# DockStation.net
KiCad netlist of a schematic drawn in Altium Designer
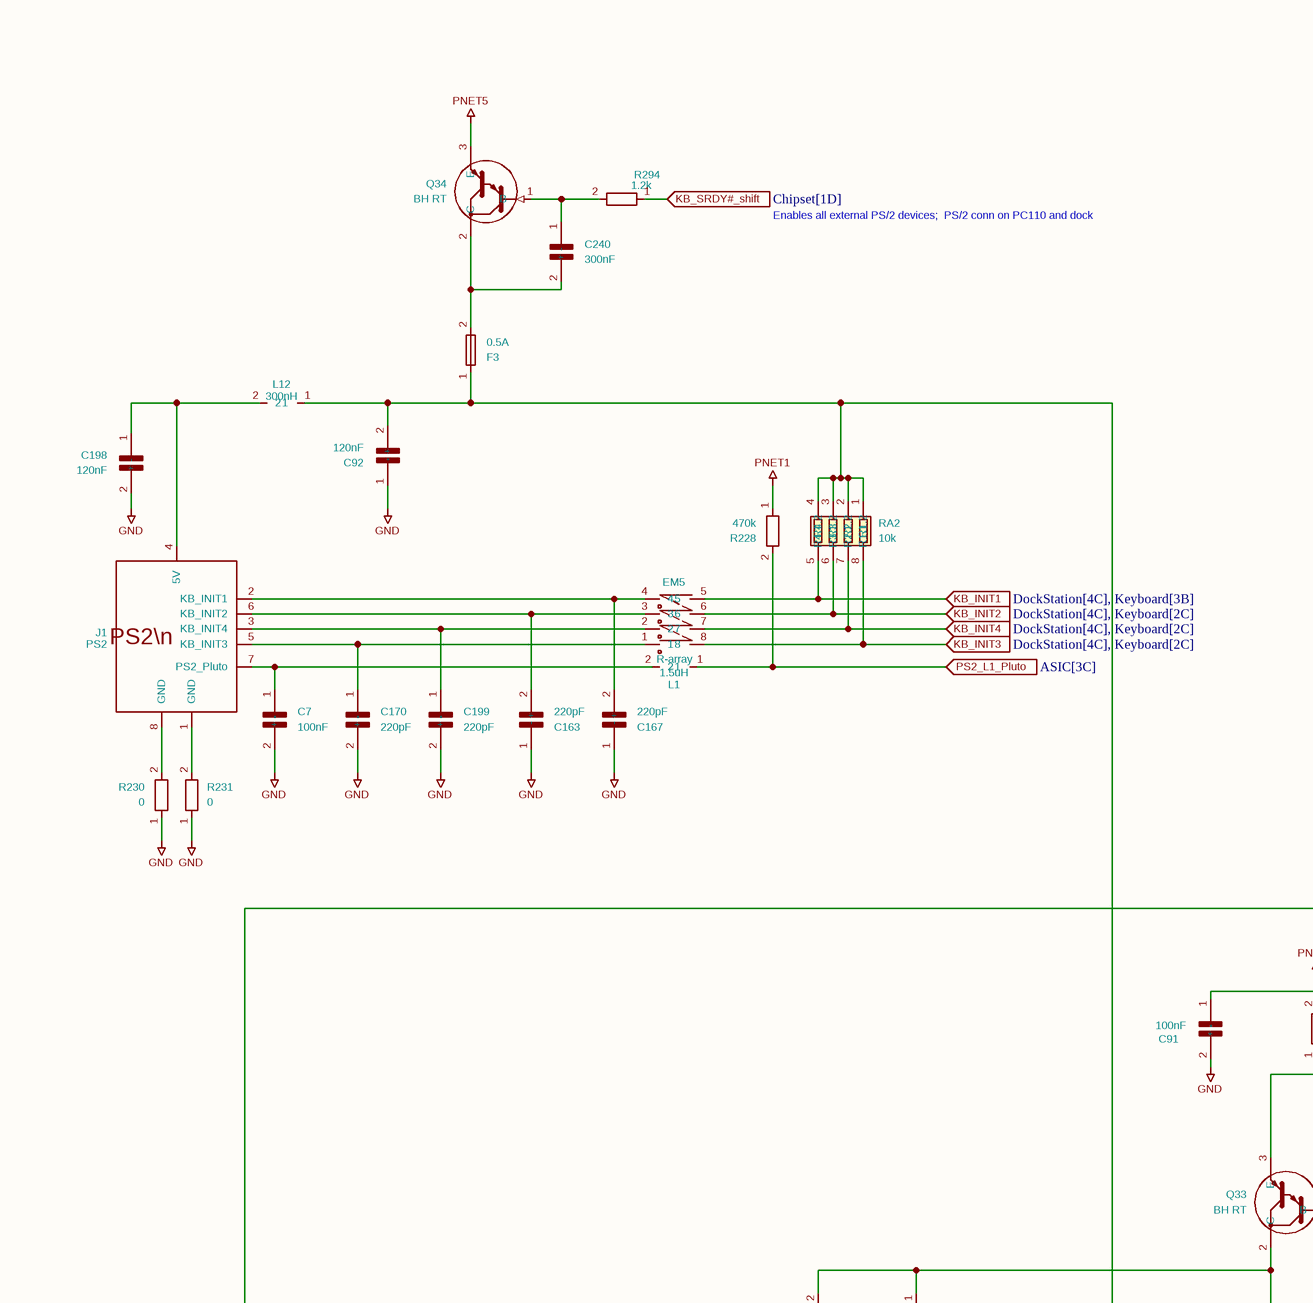
[diagram p0: DockStation.SchDoc, top left]
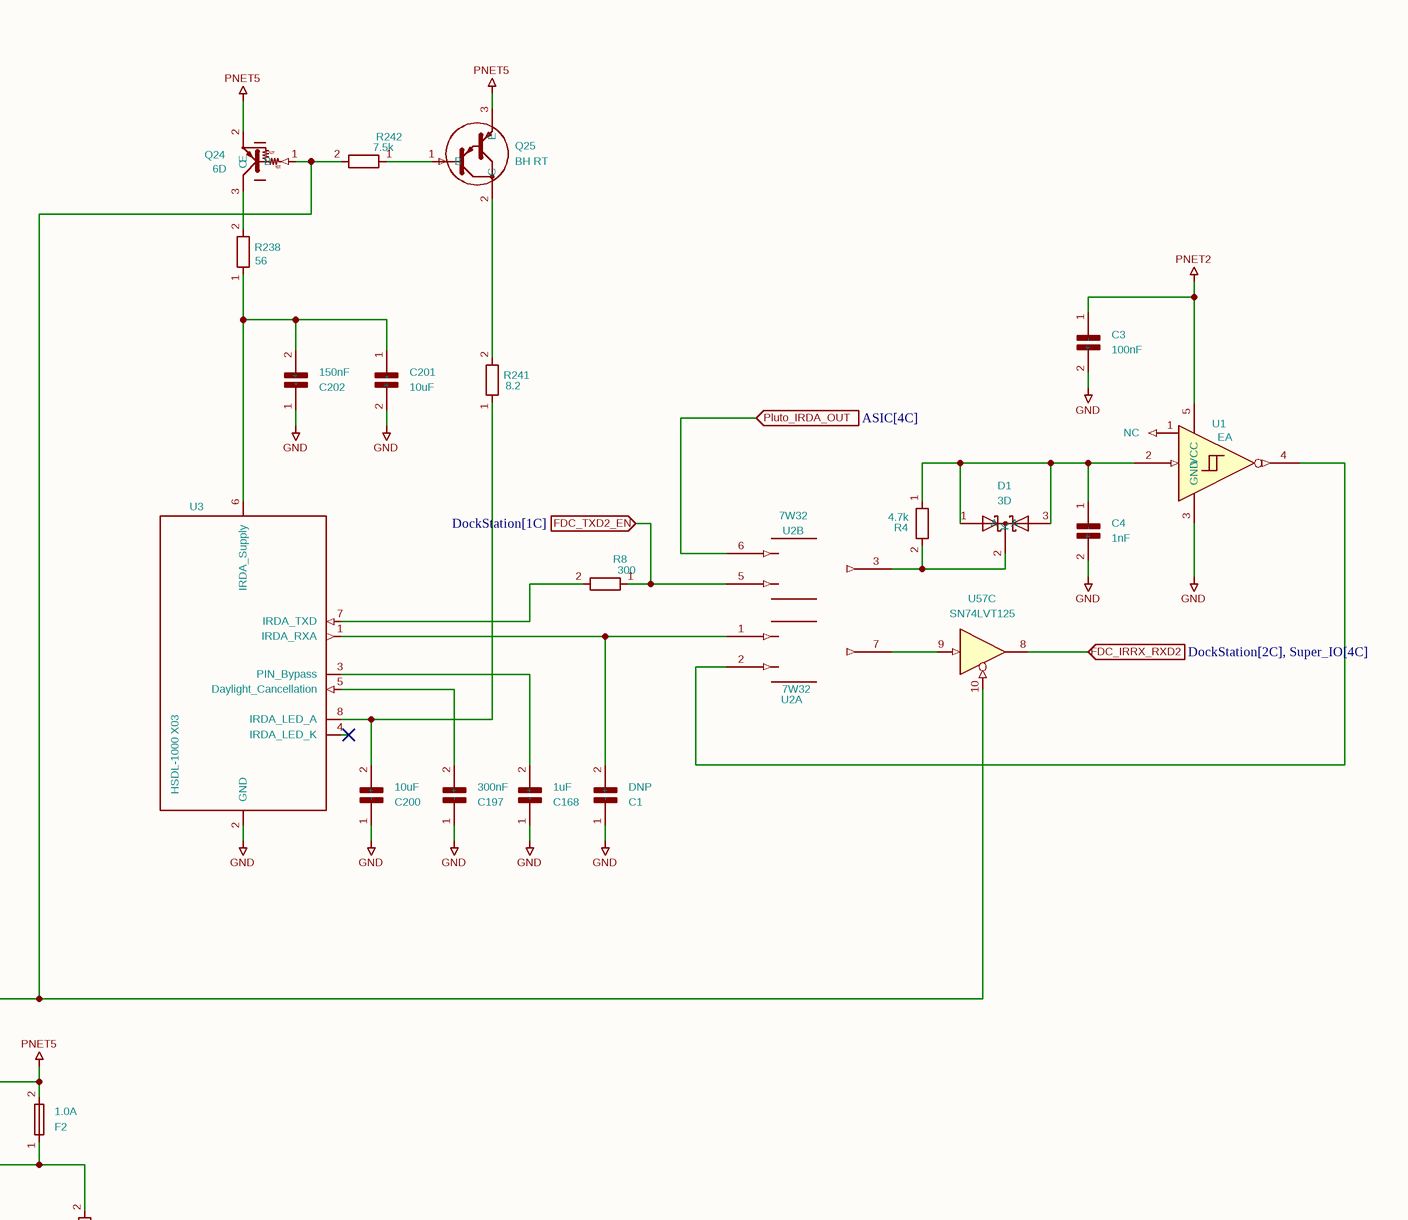
[diagram p1: DockStation.SchDoc, top middle]
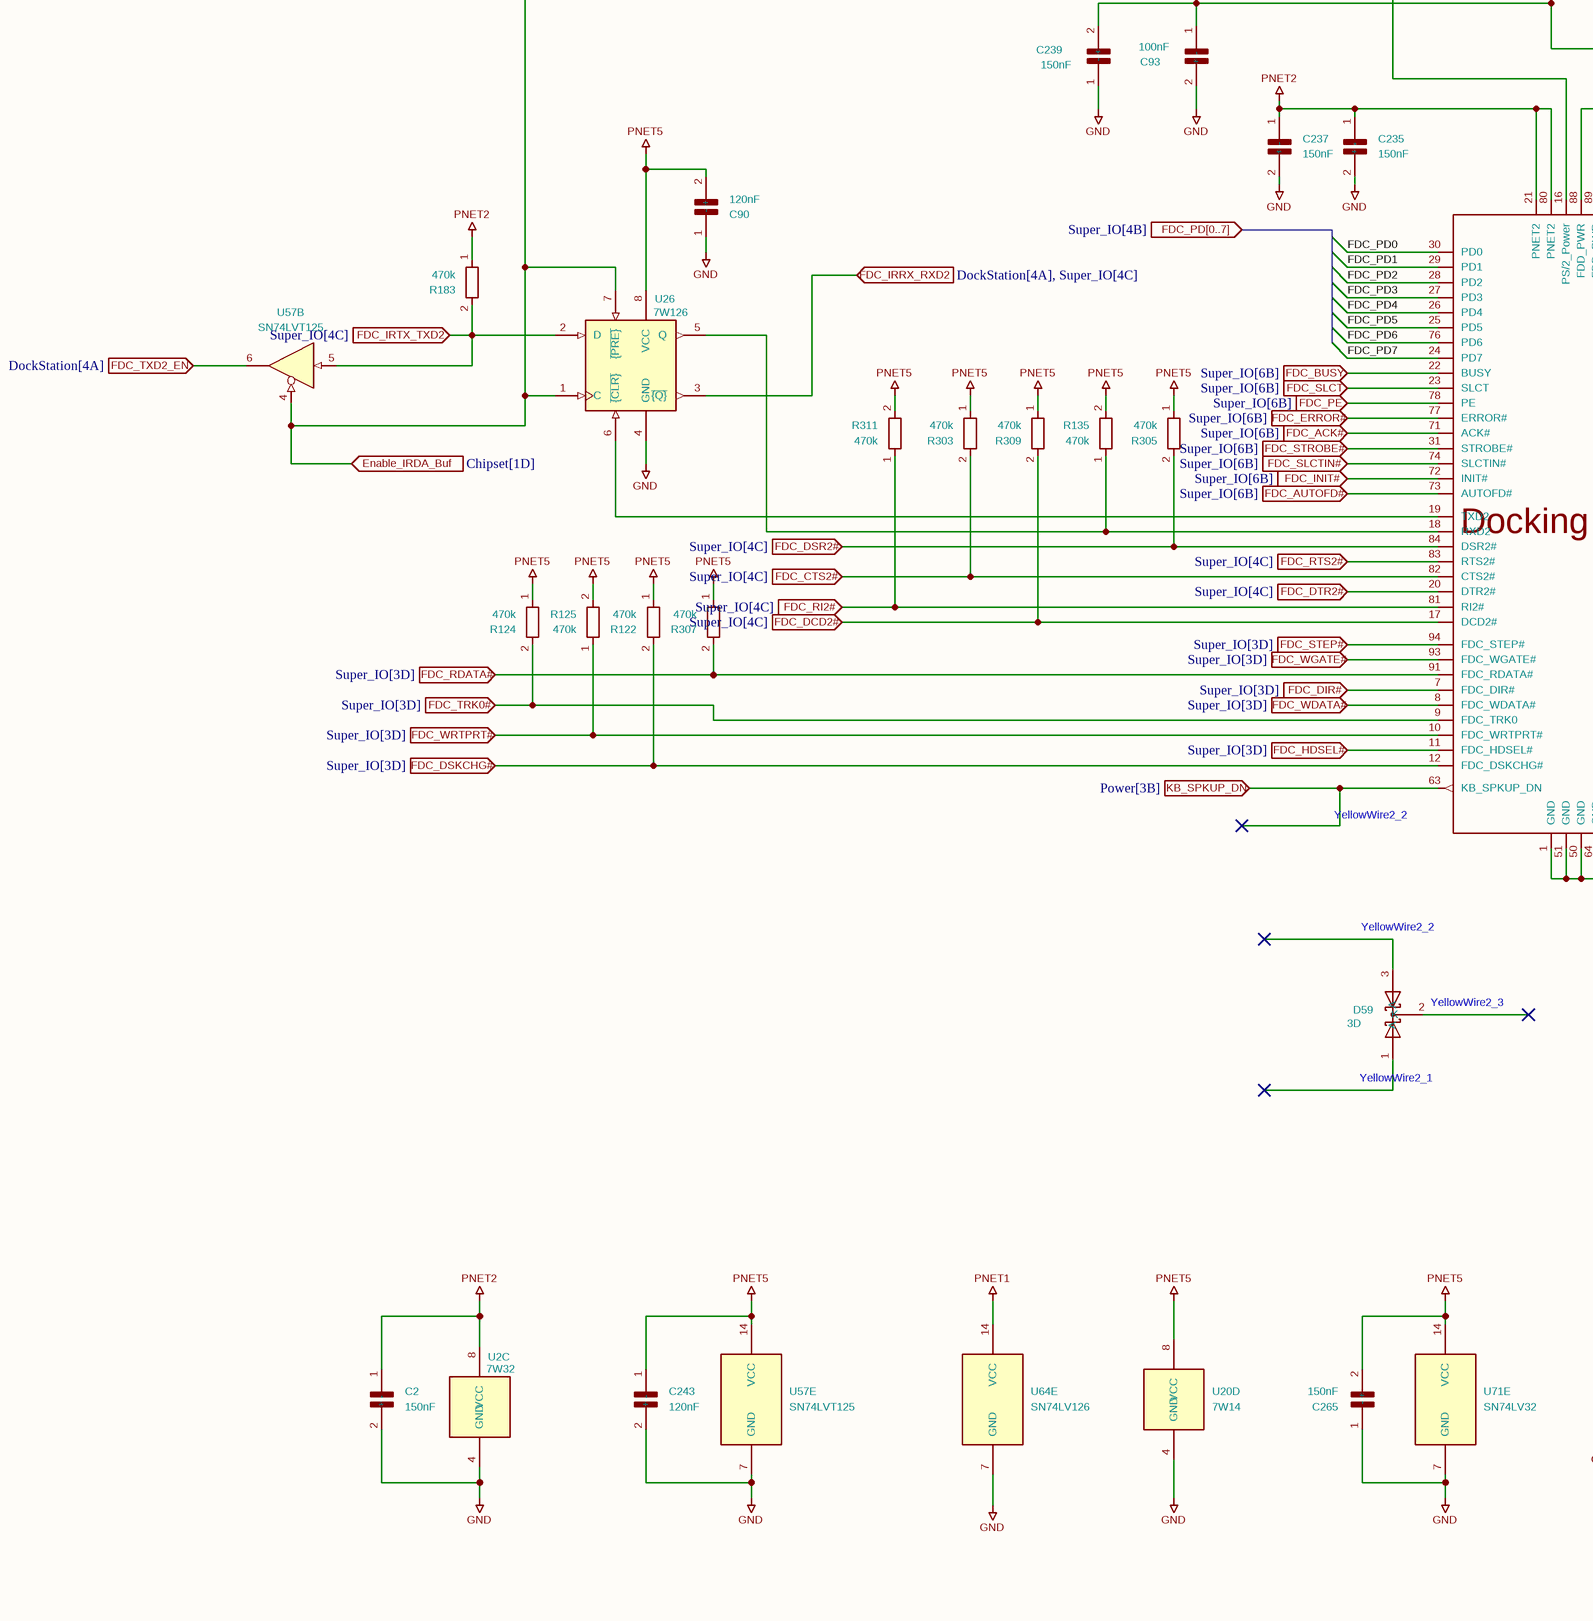
[diagram p2: DockStation.SchDoc, bottom left]
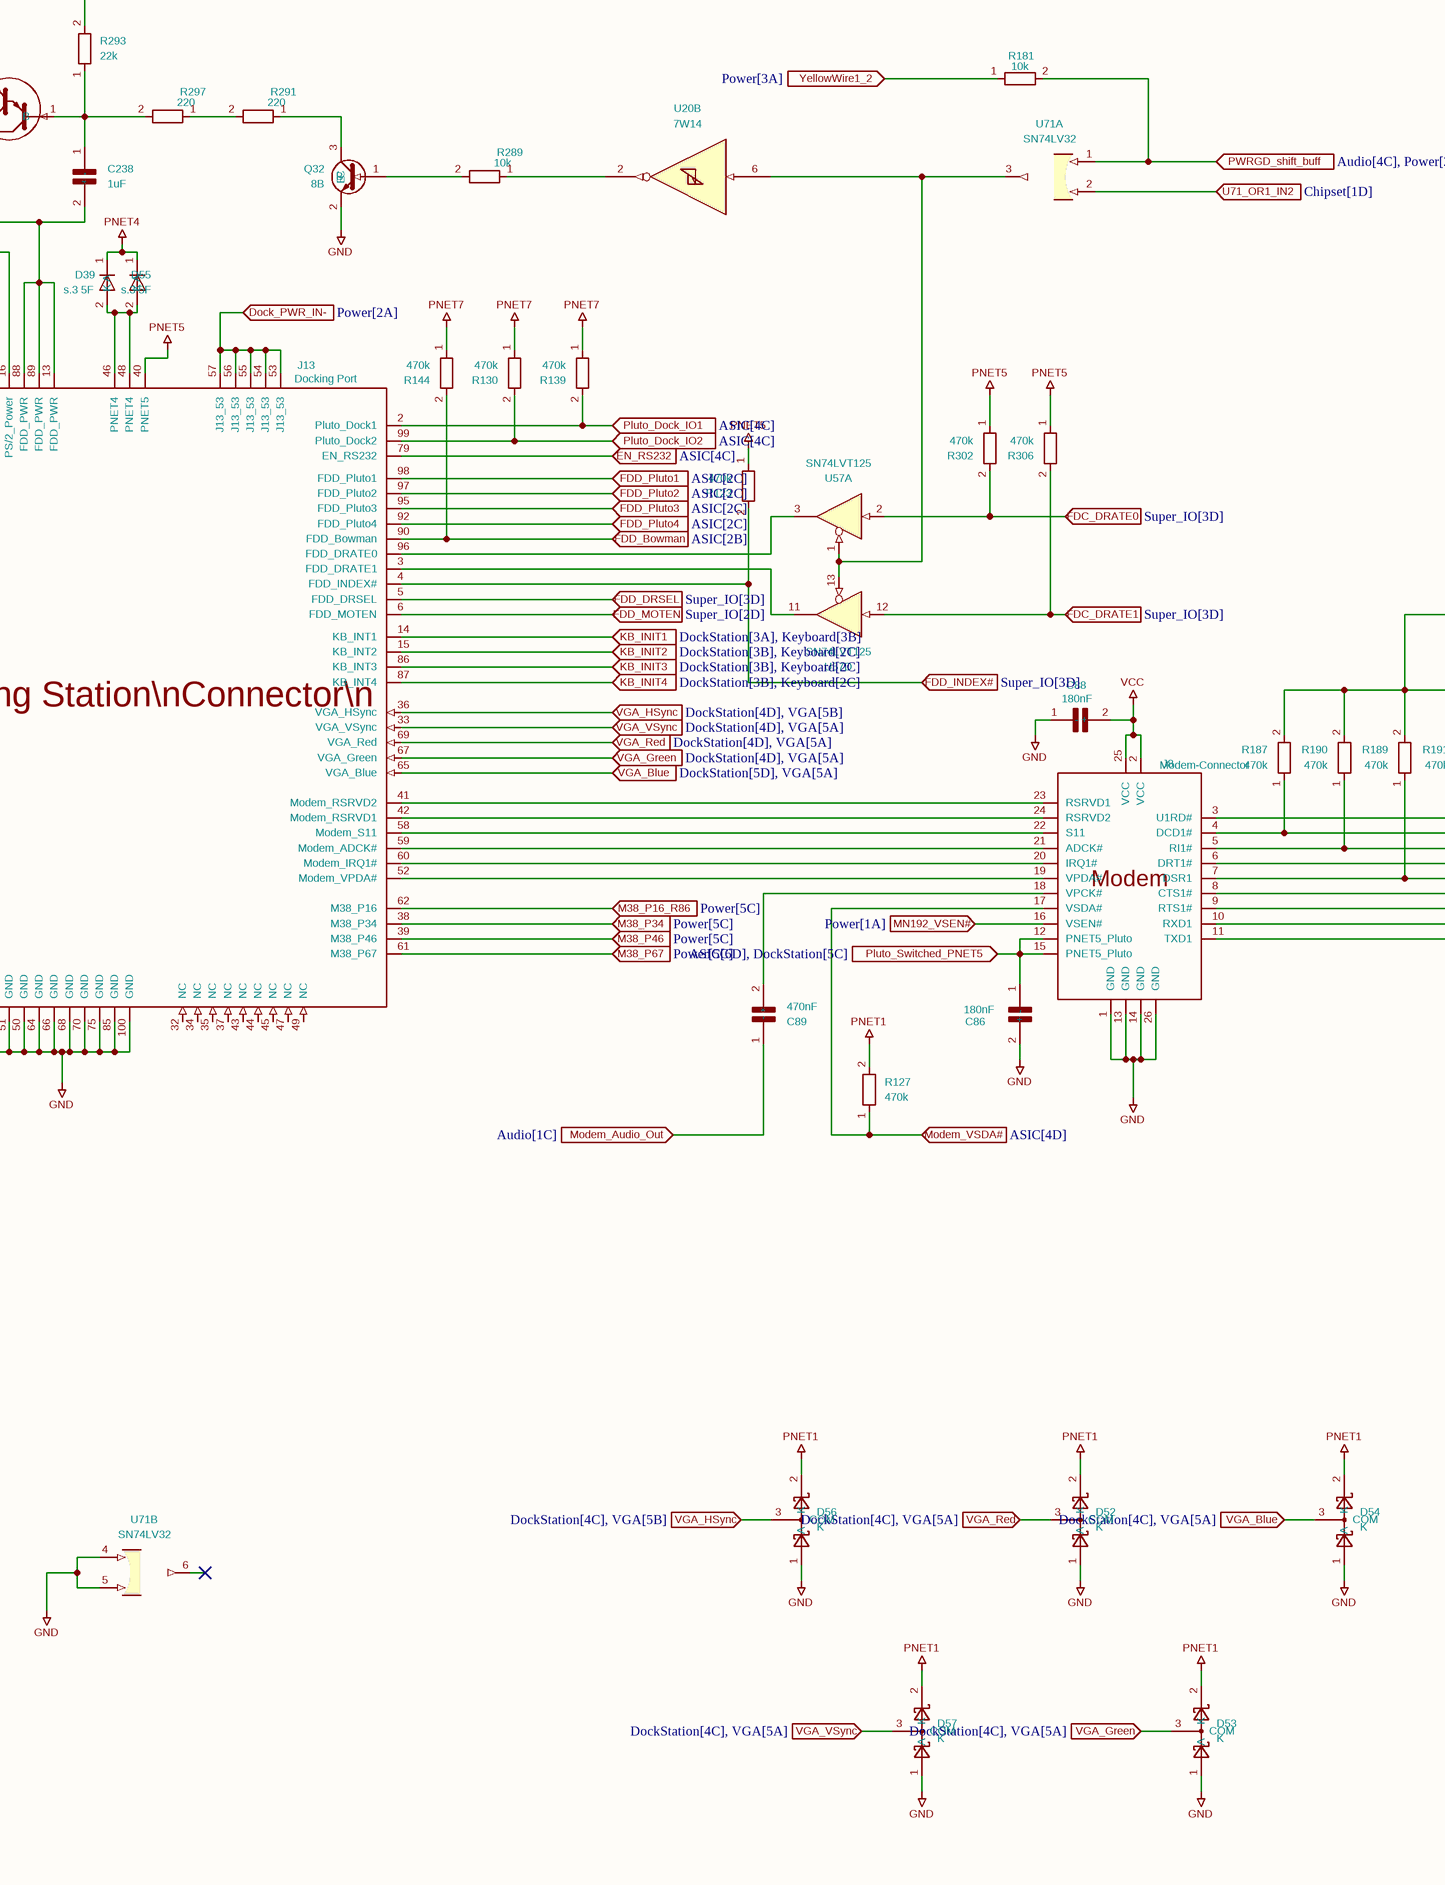
[diagram p3: DockStation.SchDoc, bottom middle]
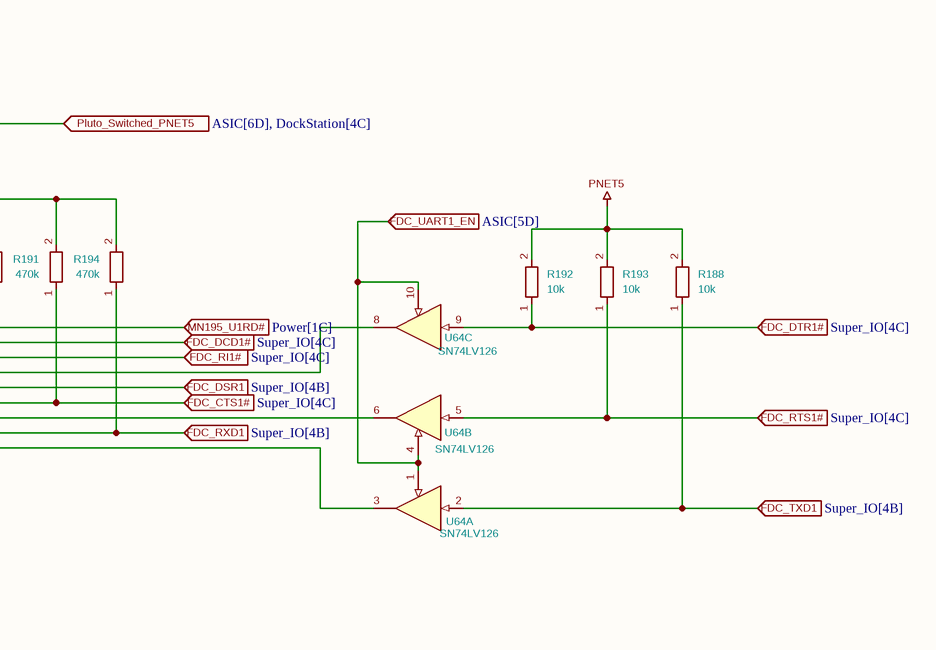
[diagram p4: DockStation.SchDoc, bottom right]

(export (version "E")
  (design (tool "Eeschema 10.0.6"))
  (components
    (comp (ref "C1") (value "DNP") (footprint "C_0402_1005Metric") (libsource (lib "") (part "C_3")))
    (comp (ref "C2")
      (value "150nF")
      (footprint "C_0402_1005Metric")
      (libsource (lib "PCM_Elektuur") (part "C"))
    )
    (comp (ref "C3")
      (value "100nF")
      (footprint "C_0402_1005Metric")
      (libsource (lib "PCM_Elektuur") (part "C"))
    )
    (comp (ref "C4")
      (value "1nF")
      (footprint "C_0402_1005Metric")
      (libsource (lib "PCM_Elektuur") (part "C"))
    )
    (comp (ref "C7")
      (value "100nF")
      (footprint "C_0402_1005Metric")
      (libsource (lib "PCM_Elektuur") (part "C"))
    )
    (comp (ref "C86") (value "180nF") (footprint "C_0402_1005Metric") (libsource (lib "") (part "C_1")))
    (comp (ref "C88") (value "180nF") (footprint "C_0402_1005Metric") (libsource (lib "") (part "C_3")))
    (comp (ref "C89") (value "470nF") (footprint "C_0603_1608Metric") (libsource (lib "") (part "C_3")))
    (comp (ref "C90") (value "120nF") (footprint "C_0402_1005Metric") (libsource (lib "") (part "C_3")))
    (comp (ref "C91") (value "100nF") (footprint "C_0402_1005Metric") (libsource (lib "") (part "C_1")))
    (comp (ref "C92") (value "120nF") (footprint "C_0402_1005Metric") (libsource (lib "") (part "C_2")))
    (comp (ref "C93") (value "100nF") (footprint "C_0402_1005Metric") (libsource (lib "") (part "C_1")))
    (comp (ref "C163") (value "220pF") (footprint "C_0402_1005Metric") (libsource (lib "") (part "C_3")))
    (comp (ref "C167") (value "220pF") (footprint "C_0402_1005Metric") (libsource (lib "") (part "C_3")))
    (comp (ref "C168") (value "1uF") (footprint "C_0603_1608Metric") (libsource (lib "") (part "C_3")))
    (comp (ref "C170")
      (value "220pF")
      (footprint "C_0402_1005Metric")
      (libsource (lib "PCM_Elektuur") (part "C"))
    )
    (comp (ref "C197") (value "300nF") (footprint "C_0603_1608Metric") (libsource (lib "") (part "C_3")))
    (comp (ref "C198") (value "120nF") (footprint "C_0402_1005Metric") (libsource (lib "") (part "C_1")))
    (comp (ref "C199")
      (value "220pF")
      (footprint "C_0402_1005Metric")
      (libsource (lib "PCM_Elektuur") (part "C"))
    )
    (comp (ref "C200") (value "10uF") (footprint "C_1206_3216Metric") (libsource (lib "") (part "C_3")))
    (comp (ref "C201")
      (value "10uF")
      (footprint "C_1206_3216Metric")
      (libsource (lib "PCM_Elektuur") (part "C"))
    )
    (comp (ref "C202") (value "150nF") (footprint "C_0603_1608Metric") (libsource (lib "") (part "C_3")))
    (comp (ref "C235")
      (value "150nF")
      (footprint "C_0402_1005Metric")
      (libsource (lib "PCM_Elektuur") (part "C"))
    )
    (comp (ref "C237")
      (value "150nF")
      (footprint "C_0402_1005Metric")
      (libsource (lib "PCM_Elektuur") (part "C"))
    )
    (comp (ref "C238")
      (value "1uF")
      (footprint "C_0603_1608Metric")
      (libsource (lib "PCM_Elektuur") (part "C"))
    )
    (comp (ref "C239") (value "150nF") (footprint "C_0402_1005Metric") (libsource (lib "") (part "C_2")))
    (comp (ref "C240")
      (value "300nF")
      (footprint "C_0603_1608Metric")
      (libsource (lib "PCM_Elektuur") (part "C"))
    )
    (comp (ref "C243")
      (value "120nF")
      (footprint "C_0402_1005Metric")
      (libsource (lib "PCM_Elektuur") (part "C"))
    )
    (comp (ref "C265") (value "150nF") (footprint "C_0402_1005Metric") (libsource (lib "") (part "C_2")))
    (comp (ref "D1")
      (value "3D")
      (footprint "3D")
      (libsource (lib "Device") (part "D_Schottky_Dual_CommonCathode_AKA"))
    )
    (comp (ref "D39") (value "s.3 5F") (footprint "Diode") (libsource (lib "Device") (part "D")))
    (comp (ref "D52") (value "K") (footprint "SOT-416") (libsource (lib "Diode") (part "BAT54SW")))
    (comp (ref "D53") (value "K") (footprint "SOT-416") (libsource (lib "Diode") (part "BAT54SW")))
    (comp (ref "D54") (value "K") (footprint "SOT-416") (libsource (lib "Diode") (part "BAT54SW")))
    (comp (ref "D55") (value "s.3 5F") (footprint "Diode") (libsource (lib "Device") (part "D")))
    (comp (ref "D56") (value "K") (footprint "SOT-416") (libsource (lib "Diode") (part "BAT54SW")))
    (comp (ref "D57") (value "K") (footprint "SOT-416") (libsource (lib "Diode") (part "BAT54SW")))
    (comp (ref "D59")
      (value "3D")
      (footprint "SOT-416L")
      (libsource (lib "Device") (part "D_Schottky_Dual_CommonCathode_AKA"))
    )
    (comp (ref "EM5")
      (value "R-array")
      (footprint "R-array")
      (libsource (lib "PC110") (part "EMI_filter_Array"))
    )
    (comp (ref "F2")
      (value "1.0A")
      (footprint "Fuse_1206_3216Metric")
      (libsource (lib "Device") (part "Fuse"))
    )
    (comp (ref "F3")
      (value "0.5A")
      (footprint "Fuse_1206_3216Metric")
      (libsource (lib "Device") (part "Fuse"))
    )
    (comp (ref "J1") (value "PS2") (footprint "PS2") (libsource (lib "PC110") (part "PS2_Conn")))
    (comp (ref "J8")
      (value "Modem-Connector")
      (footprint "Modem-Connector")
      (libsource (lib "PC110") (part "Modem_Conn"))
    )
    (comp (ref "J13")
      (value "Docking Port")
      (footprint "Docking Port")
      (libsource (lib "PC110") (part "Dock_Conn"))
    )
    (comp (ref "L1") (value "1.5uH") (footprint "L_0603_1608Metric") (libsource (lib "Device") (part "L")))
    (comp (ref "L12") (value "300nH") (footprint "L_0805_2012Metric") (libsource (lib "Device") (part "L")))
    (comp (ref "Q24") (value "6D") (footprint "SOT-23") (libsource (lib "Transistor_BJT") (part "DTA114Y")))
    (comp (ref "Q25")
      (value "BH RT")
      (footprint "SOT-89-3")
      (libsource (lib "PCM_Transistor_BJT_Darlington_AKL") (part "Q_PNP_Darlington_Generic_BCE"))
    )
    (comp (ref "Q32")
      (value "8B")
      (footprint "SOT-416")
      (libsource (lib "PCM_Transistor_BJT_AKL") (part "Q_NPN_Generic_BEC"))
    )
    (comp (ref "Q33")
      (value "BH RT")
      (footprint "SOT-89-3")
      (libsource (lib "PCM_Transistor_BJT_Darlington_AKL") (part "Q_PNP_Darlington_Generic_BCE"))
    )
    (comp (ref "Q34")
      (value "BH RT")
      (footprint "SOT-89-3")
      (libsource (lib "PCM_Transistor_BJT_Darlington_AKL") (part "Q_PNP_Darlington_Generic_BCE"))
    )
    (comp (ref "R4") (value "4.7k") (footprint "R_0402_1005Metric") (libsource (lib "") (part "R_3")))
    (comp (ref "R8") (value "300") (footprint "R_0402_1005Metric") (libsource (lib "") (part "R_3")))
    (comp (ref "R122") (value "470k") (footprint "R_0402_1005Metric") (libsource (lib "Device") (part "R")))
    (comp (ref "R123") (value "470k") (footprint "R_0402_1005Metric") (libsource (lib "Device") (part "R")))
    (comp (ref "R124") (value "470k") (footprint "R_0402_1005Metric") (libsource (lib "Device") (part "R")))
    (comp (ref "R125") (value "470k") (footprint "R_0402_1005Metric") (libsource (lib "") (part "R_1")))
    (comp (ref "R127") (value "470k") (footprint "R_0402_1005Metric") (libsource (lib "") (part "R_2")))
    (comp (ref "R130") (value "470k") (footprint "R_0402_1005Metric") (libsource (lib "Device") (part "R")))
    (comp (ref "R135") (value "470k") (footprint "R_0402_1005Metric") (libsource (lib "") (part "R_1")))
    (comp (ref "R139") (value "470k") (footprint "R_0402_1005Metric") (libsource (lib "Device") (part "R")))
    (comp (ref "R144") (value "470k") (footprint "R_0402_1005Metric") (libsource (lib "Device") (part "R")))
    (comp (ref "R181") (value "10k") (footprint "R_0402_1005Metric") (libsource (lib "") (part "R_1")))
    (comp (ref "R183") (value "470k") (footprint "R_0402_1005Metric") (libsource (lib "Device") (part "R")))
    (comp (ref "R187") (value "470k") (footprint "R_0402_1005Metric") (libsource (lib "") (part "R_1")))
    (comp (ref "R188") (value "10k") (footprint "R_0402_1005Metric") (libsource (lib "") (part "R_2")))
    (comp (ref "R189") (value "470k") (footprint "R_0402_1005Metric") (libsource (lib "") (part "R_1")))
    (comp (ref "R190") (value "470k") (footprint "R_0402_1005Metric") (libsource (lib "") (part "R_1")))
    (comp (ref "R191") (value "470k") (footprint "R_0402_1005Metric") (libsource (lib "") (part "R_1")))
    (comp (ref "R192") (value "10k") (footprint "R_0402_1005Metric") (libsource (lib "") (part "R_2")))
    (comp (ref "R193") (value "10k") (footprint "R_0402_1005Metric") (libsource (lib "") (part "R_2")))
    (comp (ref "R194") (value "470k") (footprint "R_0402_1005Metric") (libsource (lib "") (part "R_1")))
    (comp (ref "R228") (value "470k") (footprint "R_0402_1005Metric") (libsource (lib "Device") (part "R")))
    (comp (ref "R230") (value "0") (footprint "R_0805_2012Metric") (libsource (lib "") (part "R_1")))
    (comp (ref "R231") (value "0") (footprint "R_0603_1608Metric") (libsource (lib "") (part "R_2")))
    (comp (ref "R238") (value "56") (footprint "R_0603_1608Metric") (libsource (lib "") (part "R_1")))
    (comp (ref "R241")
      (value "8.2")
      (footprint "R_1206_3216Metric_Pad1.30x1.75mm_HandSolder")
      (libsource (lib "") (part "R_1"))
    )
    (comp (ref "R242") (value "7.5k") (footprint "R_0402_1005Metric") (libsource (lib "") (part "R_3")))
    (comp (ref "R289") (value "10k") (footprint "R_0402_1005Metric") (libsource (lib "") (part "R_3")))
    (comp (ref "R291") (value "220") (footprint "R_0402_1005Metric") (libsource (lib "") (part "R_3")))
    (comp (ref "R293") (value "22k") (footprint "R_0402_1005Metric") (libsource (lib "") (part "R_2")))
    (comp (ref "R294") (value "1.2k") (footprint "R_0402_1005Metric") (libsource (lib "") (part "R_3")))
    (comp (ref "R297") (value "220") (footprint "R_0402_1005Metric") (libsource (lib "") (part "R_3")))
    (comp (ref "R302") (value "470k") (footprint "R_0402_1005Metric") (libsource (lib "Device") (part "R")))
    (comp (ref "R303") (value "470k") (footprint "R_0402_1005Metric") (libsource (lib "Device") (part "R")))
    (comp (ref "R305") (value "470k") (footprint "R_0402_1005Metric") (libsource (lib "Device") (part "R")))
    (comp (ref "R306") (value "470k") (footprint "R_0402_1005Metric") (libsource (lib "Device") (part "R")))
    (comp (ref "R307") (value "470k") (footprint "R_0402_1005Metric") (libsource (lib "Device") (part "R")))
    (comp (ref "R309") (value "470k") (footprint "R_0402_1005Metric") (libsource (lib "Device") (part "R")))
    (comp (ref "R311") (value "470k") (footprint "R_0402_1005Metric") (libsource (lib "") (part "R_1")))
    (comp (ref "RA2") (value "10k") (footprint "R-array") (libsource (lib "Device") (part "R_Pack04")))
    (comp (ref "U1") (value "EA") (footprint "SOT-353") (libsource (lib "74xGxx") (part "74AHC1G14")))
    (comp (ref "U2") (value "7W32") (footprint "sso-8") (libsource (lib "") (part "74LVC2G32_1")))
    (comp (ref "U3") (value "HSDL-1000 X03") (footprint "IRDA") (libsource (lib "PC110") (part "IRDA")))
    (comp (ref "U20") (value "7W14") (footprint "sso-8") (libsource (lib "74xGxx") (part "74LVC3G14")))
    (comp (ref "U26") (value "7W126") (footprint "sso-8") (libsource (lib "74xGxx") (part "74AUC1G74")))
    (comp (ref "U57")
      (value "SN74LVT125")
      (footprint "TSSOP-14_4.4x5mm_P0.65mm")
      (libsource (lib "74xx") (part "74LS125"))
    )
    (comp (ref "U64")
      (value "SN74LV126")
      (footprint "TSSOP-14_4.4x5mm_P0.65mm")
      (libsource (lib "") (part "74LS126_2"))
    )
    (comp (ref "U71")
      (value "SN74LV32")
      (footprint "TSSOP-14_4.4x5mm_P0.65mm")
      (libsource (lib "74xx") (part "74LS32"))
    )
  )
  (nets
    (net (code "1") (name "/Dock_PWR_IN-") (class "Default")
      (node (ref "J13") (pin "53") (pinfunction "J13_53_53") (pintype "bidirectional"))
      (node (ref "J13") (pin "54") (pinfunction "J13_53_54") (pintype "bidirectional"))
      (node (ref "J13") (pin "55") (pinfunction "J13_53_55") (pintype "bidirectional"))
      (node (ref "J13") (pin "56") (pinfunction "J13_53_56") (pintype "bidirectional"))
      (node (ref "J13") (pin "57") (pinfunction "J13_53_57") (pintype "bidirectional"))
    )
    (net (code "2") (name "/EN_RS232") (class "Default")
      (node (ref "J13") (pin "79") (pinfunction "EN_RS232_79") (pintype "bidirectional"))
    )
    (net (code "3") (name "/Enable_IRDA_Buf") (class "Default")
      (node (ref "Q24") (pin "1") (pinfunction "B_1") (pintype "input"))
      (node (ref "R242") (pin "2") (pinfunction "2_2") (pintype "passive"))
      (node (ref "U26") (pin "1") (pinfunction "C_1") (pintype "input"))
      (node (ref "U26") (pin "7") (pinfunction "~{{PRE}}_7") (pintype "input"))
      (node (ref "U57") (pin "10") (pinfunction "10_10") (pintype "input"))
      (node (ref "U57") (pin "4") (pinfunction "4_4") (pintype "input"))
    )
    (net (code "4") (name "/FDC_ACK#") (class "Default")
      (node (ref "J13") (pin "71") (pinfunction "ACK#_71") (pintype "bidirectional"))
    )
    (net (code "5") (name "/FDC_AUTOFD#") (class "Default")
      (node (ref "J13") (pin "73") (pinfunction "AUTOFD#_73") (pintype "bidirectional"))
    )
    (net (code "6") (name "/FDC_BUSY") (class "Default")
      (node (ref "J13") (pin "22") (pinfunction "BUSY_22") (pintype "bidirectional"))
    )
    (net (code "7") (name "/FDC_CTS1#") (class "Default")
      (node (ref "J8") (pin "8") (pinfunction "CTS1#_8") (pintype "bidirectional"))
      (node (ref "R191") (pin "1") (pinfunction "1_1") (pintype "passive"))
    )
    (net (code "8") (name "/FDC_CTS2#") (class "Default")
      (node (ref "J13") (pin "82") (pinfunction "CTS2#_82") (pintype "bidirectional"))
      (node (ref "R303") (pin "2") (pinfunction "2_2") (pintype "passive"))
    )
    (net (code "9") (name "/FDC_DCD1#") (class "Default")
      (node (ref "J8") (pin "4") (pinfunction "DCD1#_4") (pintype "bidirectional"))
      (node (ref "R187") (pin "1") (pinfunction "1_1") (pintype "passive"))
    )
    (net (code "10") (name "/FDC_DCD2#") (class "Default")
      (node (ref "J13") (pin "17") (pinfunction "DCD2#_17") (pintype "bidirectional"))
      (node (ref "R309") (pin "2") (pinfunction "2_2") (pintype "passive"))
    )
    (net (code "11") (name "/FDC_DIR#") (class "Default")
      (node (ref "J13") (pin "7") (pinfunction "FDC_DIR#_7") (pintype "bidirectional"))
    )
    (net (code "12") (name "/FDC_DRATE0") (class "Default")
      (node (ref "R302") (pin "2") (pinfunction "2_2") (pintype "passive"))
      (node (ref "U57") (pin "2") (pinfunction "2_2") (pintype "input"))
    )
    (net (code "13") (name "/FDC_DRATE1") (class "Default")
      (node (ref "R306") (pin "2") (pinfunction "2_2") (pintype "passive"))
      (node (ref "U57") (pin "12") (pinfunction "12_12") (pintype "input"))
    )
    (net (code "14") (name "/FDC_DSKCHG#") (class "Default")
      (node (ref "J13") (pin "12") (pinfunction "FDC_DSKCHG#_12") (pintype "bidirectional"))
      (node (ref "R122") (pin "2") (pinfunction "2_2") (pintype "passive"))
    )
    (net (code "15") (name "/FDC_DSR1") (class "Default")
      (node (ref "J8") (pin "7") (pinfunction "DSR1_7") (pintype "bidirectional"))
      (node (ref "R189") (pin "1") (pinfunction "1_1") (pintype "passive"))
    )
    (net (code "16") (name "/FDC_DSR2#") (class "Default")
      (node (ref "J13") (pin "84") (pinfunction "DSR2#_84") (pintype "bidirectional"))
      (node (ref "R305") (pin "2") (pinfunction "2_2") (pintype "passive"))
    )
    (net (code "17") (name "/FDC_DTR1#") (class "Default")
      (node (ref "R192") (pin "1") (pinfunction "1_1") (pintype "passive"))
      (node (ref "U64") (pin "9") (pinfunction "9_9") (pintype "input"))
    )
    (net (code "18") (name "/FDC_DTR2#") (class "Default")
      (node (ref "J13") (pin "20") (pinfunction "DTR2#_20") (pintype "bidirectional"))
    )
    (net (code "19") (name "/FDC_ERROR#") (class "Default")
      (node (ref "J13") (pin "77") (pinfunction "ERROR#_77") (pintype "bidirectional"))
    )
    (net (code "20") (name "/FDC_HDSEL#") (class "Default")
      (node (ref "J13") (pin "11") (pinfunction "FDC_HDSEL#_11") (pintype "bidirectional"))
    )
    (net (code "21") (name "/FDC_INIT#") (class "Default")
      (node (ref "J13") (pin "72") (pinfunction "INIT#_72") (pintype "bidirectional"))
    )
    (net (code "22") (name "/FDC_IRRX_RXD2") (class "Default")
      (node (ref "U26") (pin "3") (pinfunction "~{{Q}}_3") (pintype "output"))
      (node (ref "U57") (pin "8") (pinfunction "8_8") (pintype "tri_state"))
    )
    (net (code "23") (name "/FDC_IRTX_TXD2") (class "Default")
      (node (ref "R183") (pin "2") (pinfunction "2_2") (pintype "passive"))
      (node (ref "U26") (pin "2") (pinfunction "D_2") (pintype "input"))
      (node (ref "U57") (pin "5") (pinfunction "5_5") (pintype "input"))
    )
    (net (code "24") (name "/FDC_PD0") (class "Default")
      (node (ref "J13") (pin "30") (pinfunction "PD0_30") (pintype "bidirectional"))
    )
    (net (code "25") (name "/FDC_PD1") (class "Default")
      (node (ref "J13") (pin "29") (pinfunction "PD1_29") (pintype "bidirectional"))
    )
    (net (code "26") (name "/FDC_PD2") (class "Default")
      (node (ref "J13") (pin "28") (pinfunction "PD2_28") (pintype "bidirectional"))
    )
    (net (code "27") (name "/FDC_PD3") (class "Default")
      (node (ref "J13") (pin "27") (pinfunction "PD3_27") (pintype "bidirectional"))
    )
    (net (code "28") (name "/FDC_PD4") (class "Default")
      (node (ref "J13") (pin "26") (pinfunction "PD4_26") (pintype "bidirectional"))
    )
    (net (code "29") (name "/FDC_PD5") (class "Default")
      (node (ref "J13") (pin "25") (pinfunction "PD5_25") (pintype "bidirectional"))
    )
    (net (code "30") (name "/FDC_PD6") (class "Default")
      (node (ref "J13") (pin "76") (pinfunction "PD6_76") (pintype "bidirectional"))
    )
    (net (code "31") (name "/FDC_PD7") (class "Default")
      (node (ref "J13") (pin "24") (pinfunction "PD7_24") (pintype "bidirectional"))
    )
    (net (code "33") (name "/FDC_PE") (class "Default")
      (node (ref "J13") (pin "78") (pinfunction "PE_78") (pintype "bidirectional"))
    )
    (net (code "34") (name "/FDC_RDATA#") (class "Default")
      (node (ref "J13") (pin "91") (pinfunction "FDC_RDATA#_91") (pintype "bidirectional"))
      (node (ref "R307") (pin "2") (pinfunction "2_2") (pintype "passive"))
    )
    (net (code "35") (name "/FDC_RI1#") (class "Default")
      (node (ref "J8") (pin "5") (pinfunction "RI1#_5") (pintype "bidirectional"))
      (node (ref "R190") (pin "1") (pinfunction "1_1") (pintype "passive"))
    )
    (net (code "36") (name "/FDC_RI2#") (class "Default")
      (node (ref "J13") (pin "81") (pinfunction "RI2#_81") (pintype "bidirectional"))
      (node (ref "R311") (pin "1") (pinfunction "1_1") (pintype "passive"))
    )
    (net (code "37") (name "/FDC_RTS1#") (class "Default")
      (node (ref "R193") (pin "1") (pinfunction "1_1") (pintype "passive"))
      (node (ref "U64") (pin "5") (pinfunction "5_5") (pintype "input"))
    )
    (net (code "38") (name "/FDC_RTS2#") (class "Default")
      (node (ref "J13") (pin "83") (pinfunction "RTS2#_83") (pintype "bidirectional"))
    )
    (net (code "39") (name "/FDC_RXD1") (class "Default")
      (node (ref "J8") (pin "10") (pinfunction "RXD1_10") (pintype "bidirectional"))
      (node (ref "R194") (pin "1") (pinfunction "1_1") (pintype "passive"))
    )
    (net (code "40") (name "/FDC_SLCT") (class "Default")
      (node (ref "J13") (pin "23") (pinfunction "SLCT_23") (pintype "bidirectional"))
    )
    (net (code "41") (name "/FDC_SLCTIN#") (class "Default")
      (node (ref "J13") (pin "74") (pinfunction "SLCTIN#_74") (pintype "bidirectional"))
    )
    (net (code "42") (name "/FDC_STEP#") (class "Default")
      (node (ref "J13") (pin "94") (pinfunction "FDC_STEP#_94") (pintype "bidirectional"))
    )
    (net (code "43") (name "/FDC_STROBE#") (class "Default")
      (node (ref "J13") (pin "31") (pinfunction "STROBE#_31") (pintype "bidirectional"))
    )
    (net (code "44") (name "/FDC_TRK0#") (class "Default")
      (node (ref "J13") (pin "9") (pinfunction "FDC_TRK0_9") (pintype "bidirectional"))
      (node (ref "R124") (pin "2") (pinfunction "2_2") (pintype "passive"))
    )
    (net (code "45") (name "/FDC_TXD1") (class "Default")
      (node (ref "R188") (pin "1") (pinfunction "1_1") (pintype "passive"))
      (node (ref "U64") (pin "2") (pinfunction "2_2") (pintype "input"))
    )
    (net (code "46") (name "/FDC_TXD2_EN") (class "Default")
      (node (ref "R8") (pin "1") (pinfunction "1_1") (pintype "passive"))
      (node (ref "U2") (pin "5") (pinfunction "5_5") (pintype "input"))
      (node (ref "U57") (pin "6") (pinfunction "6_6") (pintype "tri_state"))
    )
    (net (code "47") (name "/FDC_UART1_EN") (class "Default")
      (node (ref "U64") (pin "1") (pinfunction "1_1") (pintype "input"))
      (node (ref "U64") (pin "10") (pinfunction "10_10") (pintype "input"))
      (node (ref "U64") (pin "4") (pinfunction "4_4") (pintype "input"))
    )
    (net (code "48") (name "/FDC_WDATA#") (class "Default")
      (node (ref "J13") (pin "8") (pinfunction "FDC_WDATA#_8") (pintype "bidirectional"))
    )
    (net (code "49") (name "/FDC_WGATE#") (class "Default")
      (node (ref "J13") (pin "93") (pinfunction "FDC_WGATE#_93") (pintype "bidirectional"))
    )
    (net (code "50") (name "/FDC_WRTPRT#") (class "Default")
      (node (ref "J13") (pin "10") (pinfunction "FDC_WRTPRT#_10") (pintype "bidirectional"))
      (node (ref "R125") (pin "1") (pinfunction "1_1") (pintype "passive"))
    )
    (net (code "51") (name "/FDD_Bowman") (class "Default")
      (node (ref "J13") (pin "90") (pinfunction "FDD_Bowman_90") (pintype "bidirectional"))
      (node (ref "R144") (pin "2") (pinfunction "2_2") (pintype "passive"))
    )
    (net (code "52") (name "/FDD_DRSEL") (class "Default")
      (node (ref "J13") (pin "5") (pinfunction "FDD_DRSEL_5") (pintype "bidirectional"))
    )
    (net (code "53") (name "/FDD_INDEX#") (class "Default")
      (node (ref "J13") (pin "4") (pinfunction "FDD_INDEX#_4") (pintype "bidirectional"))
      (node (ref "R123") (pin "2") (pinfunction "2_2") (pintype "passive"))
    )
    (net (code "54") (name "/FDD_MOTEN") (class "Default")
      (node (ref "J13") (pin "6") (pinfunction "FDD_MOTEN_6") (pintype "bidirectional"))
    )
    (net (code "55") (name "/FDD_Pluto1") (class "Default")
      (node (ref "J13") (pin "98") (pinfunction "FDD_Pluto1_98") (pintype "bidirectional"))
    )
    (net (code "56") (name "/FDD_Pluto2") (class "Default")
      (node (ref "J13") (pin "97") (pinfunction "FDD_Pluto2_97") (pintype "bidirectional"))
    )
    (net (code "57") (name "/FDD_Pluto3") (class "Default")
      (node (ref "J13") (pin "95") (pinfunction "FDD_Pluto3_95") (pintype "bidirectional"))
    )
    (net (code "58") (name "/FDD_Pluto4") (class "Default")
      (node (ref "J13") (pin "92") (pinfunction "FDD_Pluto4_92") (pintype "bidirectional"))
    )
    (net (code "59") (name "/KB_INIT1") (class "Default")
      (node (ref "EM5") (pin "5") (pinfunction "5_5") (pintype "passive"))
      (node (ref "J13") (pin "14") (pinfunction "KB_INT1_14") (pintype "bidirectional"))
      (node (ref "RA2") (pin "5") (pinfunction "R4.2_5") (pintype "passive"))
    )
    (net (code "60") (name "/KB_INIT2") (class "Default")
      (node (ref "EM5") (pin "6") (pinfunction "6_6") (pintype "passive"))
      (node (ref "J13") (pin "15") (pinfunction "KB_INT2_15") (pintype "bidirectional"))
      (node (ref "RA2") (pin "6") (pinfunction "R3.2_6") (pintype "passive"))
    )
    (net (code "61") (name "/KB_INIT3") (class "Default")
      (node (ref "EM5") (pin "8") (pinfunction "8_8") (pintype "passive"))
      (node (ref "J13") (pin "86") (pinfunction "KB_INT3_86") (pintype "bidirectional"))
      (node (ref "RA2") (pin "8") (pinfunction "R1.2_8") (pintype "passive"))
    )
    (net (code "62") (name "/KB_INIT4") (class "Default")
      (node (ref "EM5") (pin "7") (pinfunction "7_7") (pintype "passive"))
      (node (ref "J13") (pin "87") (pinfunction "KB_INT4_87") (pintype "bidirectional"))
      (node (ref "RA2") (pin "7") (pinfunction "R2.2_7") (pintype "passive"))
    )
    (net (code "63") (name "/KB_SPKUP_DN") (class "Default")
      (node (ref "J13") (pin "63") (pinfunction "KB_SPKUP_DN_63") (pintype "output+no_connect"))
    )
    (net (code "64") (name "/KB_SRDY#_shift") (class "Default")
      (node (ref "R294") (pin "1") (pinfunction "1_1") (pintype "passive"))
    )
    (net (code "65") (name "/M38_P16_R86") (class "Default")
      (node (ref "J13") (pin "62") (pinfunction "M38_P16_62") (pintype "bidirectional"))
    )
    (net (code "66") (name "/M38_P34") (class "Default")
      (node (ref "J13") (pin "38") (pinfunction "M38_P34_38") (pintype "bidirectional"))
    )
    (net (code "67") (name "/M38_P46") (class "Default")
      (node (ref "J13") (pin "39") (pinfunction "M38_P46_39") (pintype "bidirectional"))
    )
    (net (code "68") (name "/M38_P67") (class "Default")
      (node (ref "J13") (pin "61") (pinfunction "M38_P67_61") (pintype "bidirectional"))
    )
    (net (code "69") (name "/MN192_VSEN#") (class "Default")
      (node (ref "J8") (pin "16") (pinfunction "VSEN#_16") (pintype "bidirectional"))
    )
    (net (code "70") (name "/MN195_U1RD#") (class "Default")
      (node (ref "J8") (pin "3") (pinfunction "U1RD#_3") (pintype "bidirectional"))
    )
    (net (code "71") (name "/Modem_Audio_Out") (class "Default")
      (node (ref "C89") (pin "1") (pinfunction "+_1") (pintype "passive"))
    )
    (net (code "72") (name "/Modem_VSDA#") (class "Default")
      (node (ref "J8") (pin "17") (pinfunction "VSDA#_17") (pintype "bidirectional"))
      (node (ref "R127") (pin "1") (pinfunction "1_1") (pintype "passive"))
    )
    (net (code "73") (name "/PS2_L1_Pluto") (class "Default")
      (node (ref "L1") (pin "1") (pinfunction "1_1") (pintype "passive"))
      (node (ref "R228") (pin "2") (pinfunction "2_2") (pintype "passive"))
    )
    (net (code "74") (name "/PWRGD_shift_buff") (class "Default")
      (node (ref "R181") (pin "2") (pinfunction "2_2") (pintype "passive"))
      (node (ref "U71") (pin "1") (pinfunction "1_1") (pintype "input"))
    )
    (net (code "75") (name "/Pluto_Dock_IO1") (class "Default")
      (node (ref "J13") (pin "2") (pinfunction "Pluto_Dock1_2") (pintype "bidirectional"))
      (node (ref "R139") (pin "2") (pinfunction "2_2") (pintype "passive"))
    )
    (net (code "76") (name "/Pluto_Dock_IO2") (class "Default")
      (node (ref "J13") (pin "99") (pinfunction "Pluto_Dock2_99") (pintype "bidirectional"))
      (node (ref "R130") (pin "2") (pinfunction "2_2") (pintype "passive"))
    )
    (net (code "77") (name "/Pluto_IRDA_OUT") (class "Default")
      (node (ref "U2") (pin "6") (pinfunction "6_6") (pintype "input"))
    )
    (net (code "78") (name "/Pluto_Switched_PNET5") (class "Default")
      (node (ref "C86") (pin "1") (pinfunction "+_1") (pintype "passive"))
      (node (ref "J8") (pin "12") (pinfunction "PNET5_Pluto_12") (pintype "power_in"))
      (node (ref "J8") (pin "15") (pinfunction "PNET5_Pluto_15") (pintype "power_in"))
      (node (ref "R187") (pin "2") (pinfunction "2_2") (pintype "passive"))
      (node (ref "R189") (pin "2") (pinfunction "2_2") (pintype "passive"))
      (node (ref "R190") (pin "2") (pinfunction "2_2") (pintype "passive"))
      (node (ref "R191") (pin "2") (pinfunction "2_2") (pintype "passive"))
      (node (ref "R194") (pin "2") (pinfunction "2_2") (pintype "passive"))
    )
    (net (code "79") (name "/U71_OR1_IN2") (class "Default")
      (node (ref "U71") (pin "2") (pinfunction "2_2") (pintype "input"))
    )
    (net (code "80") (name "/VGA_Blue") (class "Default")
      (node (ref "D54") (pin "3") (pinfunction "COM_3") (pintype "passive"))
      (node (ref "J13") (pin "65") (pinfunction "VGA_Blue_65") (pintype "input"))
    )
    (net (code "81") (name "/VGA_Green") (class "Default")
      (node (ref "D53") (pin "3") (pinfunction "COM_3") (pintype "passive"))
      (node (ref "J13") (pin "67") (pinfunction "VGA_Green_67") (pintype "input"))
    )
    (net (code "82") (name "/VGA_HSync") (class "Default")
      (node (ref "D56") (pin "3") (pinfunction "COM_3") (pintype "passive"))
      (node (ref "J13") (pin "36") (pinfunction "VGA_HSync_36") (pintype "input"))
    )
    (net (code "83") (name "/VGA_Red") (class "Default")
      (node (ref "D52") (pin "3") (pinfunction "COM_3") (pintype "passive"))
      (node (ref "J13") (pin "69") (pinfunction "VGA_Red_69") (pintype "input"))
    )
    (net (code "84") (name "/VGA_VSync") (class "Default")
      (node (ref "D57") (pin "3") (pinfunction "COM_3") (pintype "passive"))
      (node (ref "J13") (pin "33") (pinfunction "VGA_VSync_33") (pintype "input"))
    )
    (net (code "85") (name "/YellowWire1_2") (class "Default")
      (node (ref "R181") (pin "1") (pinfunction "1_1") (pintype "passive"))
    )
    (net (code "86") (name "GND") (class "Default")
      (node (ref "C1") (pin "1") (pinfunction "+_1") (pintype "passive"))
      (node (ref "C163") (pin "1") (pinfunction "+_1") (pintype "passive"))
      (node (ref "C167") (pin "1") (pinfunction "+_1") (pintype "passive"))
      (node (ref "C168") (pin "1") (pinfunction "+_1") (pintype "passive"))
      (node (ref "C170") (pin "2") (pinfunction "-_2") (pintype "passive"))
      (node (ref "C197") (pin "1") (pinfunction "+_1") (pintype "passive"))
      (node (ref "C198") (pin "2") (pinfunction "-_2") (pintype "passive"))
      (node (ref "C199") (pin "2") (pinfunction "-_2") (pintype "passive"))
      (node (ref "C2") (pin "2") (pinfunction "-_2") (pintype "passive"))
      (node (ref "C200") (pin "1") (pinfunction "+_1") (pintype "passive"))
      (node (ref "C201") (pin "2") (pinfunction "-_2") (pintype "passive"))
      (node (ref "C202") (pin "1") (pinfunction "+_1") (pintype "passive"))
      (node (ref "C235") (pin "2") (pinfunction "-_2") (pintype "passive"))
      (node (ref "C237") (pin "2") (pinfunction "-_2") (pintype "passive"))
      (node (ref "C239") (pin "1") (pinfunction "+_1") (pintype "passive"))
      (node (ref "C243") (pin "2") (pinfunction "-_2") (pintype "passive"))
      (node (ref "C265") (pin "1") (pinfunction "+_1") (pintype "passive"))
      (node (ref "C3") (pin "2") (pinfunction "-_2") (pintype "passive"))
      (node (ref "C4") (pin "2") (pinfunction "-_2") (pintype "passive"))
      (node (ref "C7") (pin "2") (pinfunction "-_2") (pintype "passive"))
      (node (ref "C86") (pin "2") (pinfunction "-_2") (pintype "passive"))
      (node (ref "C88") (pin "1") (pinfunction "+_1") (pintype "passive"))
      (node (ref "C90") (pin "1") (pinfunction "+_1") (pintype "passive"))
      (node (ref "C91") (pin "2") (pinfunction "-_2") (pintype "passive"))
      (node (ref "C92") (pin "1") (pinfunction "+_1") (pintype "passive"))
      (node (ref "C93") (pin "2") (pinfunction "-_2") (pintype "passive"))
      (node (ref "D52") (pin "1") (pinfunction "A_1") (pintype "passive"))
      (node (ref "D53") (pin "1") (pinfunction "A_1") (pintype "passive"))
      (node (ref "D54") (pin "1") (pinfunction "A_1") (pintype "passive"))
      (node (ref "D56") (pin "1") (pinfunction "A_1") (pintype "passive"))
      (node (ref "D57") (pin "1") (pinfunction "A_1") (pintype "passive"))
      (node (ref "J13") (pin "1") (pinfunction "GND_1") (pintype "power_in"))
      (node (ref "J13") (pin "100") (pinfunction "GND_100") (pintype "power_in"))
      (node (ref "J13") (pin "50") (pinfunction "GND_50") (pintype "power_in"))
      (node (ref "J13") (pin "51") (pinfunction "GND_51") (pintype "power_in"))
      (node (ref "J13") (pin "64") (pinfunction "GND_64") (pintype "power_in"))
      (node (ref "J13") (pin "66") (pinfunction "GND_66") (pintype "power_in"))
      (node (ref "J13") (pin "68") (pinfunction "GND_68") (pintype "power_in"))
      (node (ref "J13") (pin "70") (pinfunction "GND_70") (pintype "power_in"))
      (node (ref "J13") (pin "75") (pinfunction "GND_75") (pintype "power_in"))
      (node (ref "J13") (pin "85") (pinfunction "GND_85") (pintype "power_in"))
      (node (ref "J8") (pin "1") (pinfunction "GND_1") (pintype "power_in"))
      (node (ref "J8") (pin "13") (pinfunction "GND_13") (pintype "power_in"))
      (node (ref "J8") (pin "14") (pinfunction "GND_14") (pintype "power_in"))
      (node (ref "J8") (pin "26") (pinfunction "GND_26") (pintype "power_in"))
      (node (ref "Q32") (pin "2") (pinfunction "E_2") (pintype "passive"))
      (node (ref "R230") (pin "1") (pinfunction "1_1") (pintype "passive"))
      (node (ref "R231") (pin "1") (pinfunction "1_1") (pintype "passive"))
      (node (ref "U1") (pin "3") (pinfunction "GND_3") (pintype "power_in"))
      (node (ref "U2") (pin "4") (pinfunction "GND_4") (pintype "power_in"))
      (node (ref "U20") (pin "4") (pinfunction "GND_4") (pintype "power_in"))
      (node (ref "U26") (pin "4") (pinfunction "GND_4") (pintype "power_in"))
      (node (ref "U3") (pin "2") (pinfunction "GND_2") (pintype "power_in"))
      (node (ref "U57") (pin "7") (pinfunction "GND_7") (pintype "power_in"))
      (node (ref "U64") (pin "7") (pinfunction "GND_7") (pintype "power_in"))
      (node (ref "U71") (pin "4") (pinfunction "4_4") (pintype "input"))
      (node (ref "U71") (pin "5") (pinfunction "5_5") (pintype "input"))
      (node (ref "U71") (pin "7") (pinfunction "GND_7") (pintype "power_in"))
    )
    (net (code "87") (name "Net-(C1--)") (class "Default")
      (node (ref "C1") (pin "2") (pinfunction "-_2") (pintype "passive"))
      (node (ref "U2") (pin "1") (pinfunction "1_1") (pintype "input"))
      (node (ref "U3") (pin "1") (pinfunction "IRDA_RXA_1") (pintype "output"))
    )
    (net (code "88") (name "Net-(C4-+)") (class "Default")
      (node (ref "C4") (pin "1") (pinfunction "+_1") (pintype "passive"))
      (node (ref "D1") (pin "1") (pinfunction "A_1") (pintype "passive"))
      (node (ref "D1") (pin "3") (pinfunction "A_3") (pintype "passive"))
      (node (ref "R4") (pin "1") (pinfunction "1_1") (pintype "passive"))
      (node (ref "U1") (pin "2") (pinfunction "2_2") (pintype "input"))
    )
    (net (code "89") (name "Net-(C7-+)") (class "Default")
      (node (ref "C7") (pin "1") (pinfunction "+_1") (pintype "passive"))
      (node (ref "J1") (pin "7") (pinfunction "PS2_Pluto_7") (pintype "bidirectional"))
      (node (ref "L1") (pin "2") (pinfunction "2_2") (pintype "passive"))
    )
    (net (code "90") (name "Net-(C89--)") (class "Default")
      (node (ref "C89") (pin "2") (pinfunction "-_2") (pintype "passive"))
      (node (ref "J8") (pin "18") (pinfunction "VPCK#_18") (pintype "bidirectional"))
    )
    (net (code "91") (name "Net-(C92--)") (class "Default")
      (node (ref "C92") (pin "2") (pinfunction "-_2") (pintype "passive"))
      (node (ref "F3") (pin "1") (pinfunction "1_1") (pintype "passive"))
      (node (ref "J13") (pin "16") (pinfunction "PS/2_Power_16") (pintype "power_in"))
      (node (ref "L12") (pin "1") (pinfunction "1_1") (pintype "passive"))
      (node (ref "RA2") (pin "1") (pinfunction "R1.1_1") (pintype "passive"))
      (node (ref "RA2") (pin "2") (pinfunction "R2.1_2") (pintype "passive"))
      (node (ref "RA2") (pin "3") (pinfunction "R3.1_3") (pintype "passive"))
      (node (ref "RA2") (pin "4") (pinfunction "R4.1_4") (pintype "passive"))
    )
    (net (code "92") (name "Net-(C163--)") (class "Default")
      (node (ref "C163") (pin "2") (pinfunction "-_2") (pintype "passive"))
      (node (ref "EM5") (pin "3") (pinfunction "3_3") (pintype "passive"))
      (node (ref "J1") (pin "6") (pinfunction "KB_INIT2_6") (pintype "bidirectional"))
    )
    (net (code "93") (name "Net-(C167--)") (class "Default")
      (node (ref "C167") (pin "2") (pinfunction "-_2") (pintype "passive"))
      (node (ref "EM5") (pin "4") (pinfunction "4_4") (pintype "passive"))
      (node (ref "J1") (pin "2") (pinfunction "KB_INIT1_2") (pintype "bidirectional"))
    )
    (net (code "94") (name "Net-(C168--)") (class "Default")
      (node (ref "C168") (pin "2") (pinfunction "-_2") (pintype "passive"))
      (node (ref "U3") (pin "3") (pinfunction "PIN_Bypass_3") (pintype "passive"))
    )
    (net (code "95") (name "Net-(C170-+)") (class "Default")
      (node (ref "C170") (pin "1") (pinfunction "+_1") (pintype "passive"))
      (node (ref "EM5") (pin "1") (pinfunction "1_1") (pintype "passive"))
      (node (ref "J1") (pin "5") (pinfunction "KB_INIT3_5") (pintype "bidirectional"))
    )
    (net (code "96") (name "Net-(C197--)") (class "Default")
      (node (ref "C197") (pin "2") (pinfunction "-_2") (pintype "passive"))
      (node (ref "U3") (pin "5") (pinfunction "Daylight_Cancellation_5") (pintype "input"))
    )
    (net (code "97") (name "Net-(C198-+)") (class "Default")
      (node (ref "C198") (pin "1") (pinfunction "+_1") (pintype "passive"))
      (node (ref "J1") (pin "4") (pinfunction "5V_4") (pintype "power_in"))
      (node (ref "L12") (pin "2") (pinfunction "2_2") (pintype "passive"))
    )
    (net (code "98") (name "Net-(C199-+)") (class "Default")
      (node (ref "C199") (pin "1") (pinfunction "+_1") (pintype "passive"))
      (node (ref "EM5") (pin "2") (pinfunction "2_2") (pintype "passive"))
      (node (ref "J1") (pin "3") (pinfunction "KB_INIT4_3") (pintype "bidirectional"))
    )
    (net (code "99") (name "Net-(C200--)") (class "Default")
      (node (ref "C200") (pin "2") (pinfunction "-_2") (pintype "passive"))
      (node (ref "R241") (pin "1") (pinfunction "1_1") (pintype "passive"))
      (node (ref "U3") (pin "8") (pinfunction "IRDA_LED_A_8") (pintype "power_in"))
    )
    (net (code "100") (name "Net-(C201-+)") (class "Default")
      (node (ref "C201") (pin "1") (pinfunction "+_1") (pintype "passive"))
      (node (ref "C202") (pin "2") (pinfunction "-_2") (pintype "passive"))
      (node (ref "R238") (pin "1") (pinfunction "1_1") (pintype "passive"))
      (node (ref "U3") (pin "6") (pinfunction "IRDA_Supply_6") (pintype "power_in"))
    )
    (net (code "101") (name "Net-(C238-+)") (class "Default")
      (node (ref "C238") (pin "1") (pinfunction "+_1") (pintype "passive"))
      (node (ref "Q33") (pin "1") (pinfunction "B_1") (pintype "input"))
      (node (ref "R293") (pin "1") (pinfunction "1_1") (pintype "passive"))
      (node (ref "R297") (pin "2") (pinfunction "2_2") (pintype "passive"))
    )
    (net (code "102") (name "Net-(C238--)") (class "Default")
      (node (ref "C238") (pin "2") (pinfunction "-_2") (pintype "passive"))
      (node (ref "C239") (pin "2") (pinfunction "-_2") (pintype "passive"))
      (node (ref "C93") (pin "1") (pinfunction "+_1") (pintype "passive"))
      (node (ref "J13") (pin "13") (pinfunction "FDD_PWR_13") (pintype "power_in"))
      (node (ref "J13") (pin "88") (pinfunction "FDD_PWR_88") (pintype "power_in"))
      (node (ref "J13") (pin "89") (pinfunction "FDD_PWR_89") (pintype "power_in"))
      (node (ref "Q33") (pin "2") (pinfunction "C_2") (pintype "passive"))
    )
    (net (code "103") (name "Net-(C240-+)") (class "Default")
      (node (ref "C240") (pin "1") (pinfunction "+_1") (pintype "passive"))
      (node (ref "Q34") (pin "1") (pinfunction "B_1") (pintype "input"))
      (node (ref "R294") (pin "2") (pinfunction "2_2") (pintype "passive"))
    )
    (net (code "104") (name "Net-(C240--)") (class "Default")
      (node (ref "C240") (pin "2") (pinfunction "-_2") (pintype "passive"))
      (node (ref "F3") (pin "2") (pinfunction "2_2") (pintype "passive"))
      (node (ref "Q34") (pin "2") (pinfunction "C_2") (pintype "passive"))
    )
    (net (code "105") (name "Net-(D1-K)") (class "Default")
      (node (ref "D1") (pin "2") (pinfunction "K_2") (pintype "passive"))
      (node (ref "R4") (pin "2") (pinfunction "2_2") (pintype "passive"))
      (node (ref "U2") (pin "3") (pinfunction "3_3") (pintype "output"))
    )
    (net (code "106") (name "Net-(D39-A)") (class "Default")
      (node (ref "D39") (pin "2") (pinfunction "A_2") (pintype "passive"))
      (node (ref "D55") (pin "2") (pinfunction "A_2") (pintype "passive"))
      (node (ref "J13") (pin "46") (pinfunction "PNET4_46") (pintype "power_in"))
      (node (ref "J13") (pin "48") (pinfunction "PNET4_48") (pintype "power_in"))
    )
    (net (code "107") (name "Net-(J1-GND-Pad1)") (class "Default")
      (node (ref "J1") (pin "1") (pinfunction "GND_1") (pintype "power_in"))
      (node (ref "R231") (pin "2") (pinfunction "2_2") (pintype "passive"))
    )
    (net (code "108") (name "Net-(J1-GND-Pad8)") (class "Default")
      (node (ref "J1") (pin "8") (pinfunction "GND_8") (pintype "power_in"))
      (node (ref "R230") (pin "2") (pinfunction "2_2") (pintype "passive"))
    )
    (net (code "109") (name "Net-(J8-DRT1#)") (class "Default")
      (node (ref "J8") (pin "6") (pinfunction "DRT1#_6") (pintype "bidirectional"))
      (node (ref "U64") (pin "8") (pinfunction "8_8") (pintype "tri_state"))
    )
    (net (code "110") (name "Net-(J8-RTS1#)") (class "Default")
      (node (ref "J8") (pin "9") (pinfunction "RTS1#_9") (pintype "bidirectional"))
      (node (ref "U64") (pin "6") (pinfunction "6_6") (pintype "tri_state"))
    )
    (net (code "111") (name "Net-(J8-TXD1)") (class "Default")
      (node (ref "J8") (pin "11") (pinfunction "TXD1_11") (pintype "bidirectional"))
      (node (ref "U64") (pin "3") (pinfunction "3_3") (pintype "tri_state"))
    )
    (net (code "112") (name "Net-(J13-FDD_DRATE0)") (class "Default")
      (node (ref "J13") (pin "96") (pinfunction "FDD_DRATE0_96") (pintype "bidirectional"))
      (node (ref "U57") (pin "3") (pinfunction "3_3") (pintype "tri_state"))
    )
    (net (code "113") (name "Net-(J13-FDD_DRATE1)") (class "Default")
      (node (ref "J13") (pin "3") (pinfunction "FDD_DRATE1_3") (pintype "bidirectional"))
      (node (ref "U57") (pin "11") (pinfunction "11_11") (pintype "tri_state"))
    )
    (net (code "114") (name "Net-(J13-Modem_ADCK#)") (class "Default")
      (node (ref "J13") (pin "59") (pinfunction "Modem_ADCK#_59") (pintype "bidirectional"))
      (node (ref "J8") (pin "21") (pinfunction "ADCK#_21") (pintype "bidirectional"))
    )
    (net (code "115") (name "Net-(J13-Modem_IRQ1#)") (class "Default")
      (node (ref "J13") (pin "60") (pinfunction "Modem_IRQ1#_60") (pintype "bidirectional"))
      (node (ref "J8") (pin "20") (pinfunction "IRQ1#_20") (pintype "bidirectional"))
    )
    (net (code "116") (name "Net-(J13-Modem_RSRVD1)") (class "Default")
      (node (ref "J13") (pin "42") (pinfunction "Modem_RSRVD1_42") (pintype "bidirectional"))
      (node (ref "J8") (pin "24") (pinfunction "RSRVD2_24") (pintype "bidirectional"))
    )
    (net (code "117") (name "Net-(J13-Modem_RSRVD2)") (class "Default")
      (node (ref "J13") (pin "41") (pinfunction "Modem_RSRVD2_41") (pintype "bidirectional"))
      (node (ref "J8") (pin "23") (pinfunction "RSRVD1_23") (pintype "bidirectional"))
    )
    (net (code "118") (name "Net-(J13-Modem_S11)") (class "Default")
      (node (ref "J13") (pin "58") (pinfunction "Modem_S11_58") (pintype "bidirectional"))
      (node (ref "J8") (pin "22") (pinfunction "S11_22") (pintype "bidirectional"))
    )
    (net (code "119") (name "Net-(J13-Modem_VPDA#)") (class "Default")
      (node (ref "J13") (pin "52") (pinfunction "Modem_VPDA#_52") (pintype "bidirectional"))
      (node (ref "J8") (pin "19") (pinfunction "VPDA#_19") (pintype "bidirectional"))
    )
    (net (code "120") (name "Net-(J13-RXD2)") (class "Default")
      (node (ref "J13") (pin "18") (pinfunction "RXD2_18") (pintype "bidirectional"))
      (node (ref "R135") (pin "1") (pinfunction "1_1") (pintype "passive"))
      (node (ref "U26") (pin "5") (pinfunction "Q_5") (pintype "output"))
    )
    (net (code "121") (name "Net-(J13-TXD2)") (class "Default")
      (node (ref "J13") (pin "19") (pinfunction "TXD2_19") (pintype "bidirectional"))
      (node (ref "U26") (pin "6") (pinfunction "~{{CLR}}_6") (pintype "input"))
    )
    (net (code "122") (name "Net-(Q24-C)") (class "Default")
      (node (ref "Q24") (pin "3") (pinfunction "C_3") (pintype "passive"))
      (node (ref "R238") (pin "2") (pinfunction "2_2") (pintype "passive"))
    )
    (net (code "123") (name "Net-(Q25-B)") (class "Default")
      (node (ref "Q25") (pin "1") (pinfunction "B_1") (pintype "input"))
      (node (ref "R242") (pin "1") (pinfunction "1_1") (pintype "passive"))
    )
    (net (code "124") (name "Net-(Q25-C)") (class "Default")
      (node (ref "Q25") (pin "2") (pinfunction "C_2") (pintype "passive"))
      (node (ref "R241") (pin "2") (pinfunction "2_2") (pintype "passive"))
    )
    (net (code "125") (name "Net-(Q32-B)") (class "Default")
      (node (ref "Q32") (pin "1") (pinfunction "B_1") (pintype "input"))
      (node (ref "R289") (pin "2") (pinfunction "2_2") (pintype "passive"))
    )
    (net (code "126") (name "Net-(Q32-C)") (class "Default")
      (node (ref "Q32") (pin "3") (pinfunction "C_3") (pintype "passive"))
      (node (ref "R291") (pin "1") (pinfunction "1_1") (pintype "passive"))
    )
    (net (code "127") (name "Net-(Q33-E)") (class "Default")
      (node (ref "F2") (pin "1") (pinfunction "1_1") (pintype "passive"))
      (node (ref "Q33") (pin "3") (pinfunction "E_3") (pintype "passive"))
      (node (ref "R293") (pin "2") (pinfunction "2_2") (pintype "passive"))
    )
    (net (code "128") (name "Net-(R289-Pad1)") (class "Default")
      (node (ref "R289") (pin "1") (pinfunction "1_1") (pintype "passive"))
      (node (ref "U20") (pin "2") (pinfunction "2_2") (pintype "output"))
    )
    (net (code "129") (name "Net-(R291-Pad2)") (class "Default")
      (node (ref "R291") (pin "2") (pinfunction "2_2") (pintype "passive"))
      (node (ref "R297") (pin "1") (pinfunction "1_1") (pintype "passive"))
    )
    (net (code "130") (name "Net-(U1-Pad4)") (class "Default")
      (node (ref "U1") (pin "4") (pinfunction "4_4") (pintype "output"))
      (node (ref "U2") (pin "2") (pinfunction "2_2") (pintype "input"))
    )
    (net (code "131") (name "Net-(U2-Pad7)") (class "Default")
      (node (ref "U2") (pin "7") (pinfunction "7_7") (pintype "output"))
      (node (ref "U57") (pin "9") (pinfunction "9_9") (pintype "input"))
    )
    (net (code "132") (name "Net-(U3-IRDA_TXD)") (class "Default")
      (node (ref "R8") (pin "2") (pinfunction "2_2") (pintype "passive"))
      (node (ref "U3") (pin "7") (pinfunction "IRDA_TXD_7") (pintype "input"))
    )
    (net (code "133") (name "Net-(U20-Pad6)") (class "Default")
      (node (ref "U20") (pin "6") (pinfunction "6_6") (pintype "input"))
      (node (ref "U57") (pin "1") (pinfunction "1_1") (pintype "input"))
      (node (ref "U57") (pin "13") (pinfunction "13_13") (pintype "input"))
      (node (ref "U71") (pin "3") (pinfunction "3_3") (pintype "output"))
    )
    (net (code "134") (name "PNET1") (class "Default")
      (node (ref "D52") (pin "2") (pinfunction "K_2") (pintype "passive"))
      (node (ref "D53") (pin "2") (pinfunction "K_2") (pintype "passive"))
      (node (ref "D54") (pin "2") (pinfunction "K_2") (pintype "passive"))
      (node (ref "D56") (pin "2") (pinfunction "K_2") (pintype "passive"))
      (node (ref "D57") (pin "2") (pinfunction "K_2") (pintype "passive"))
      (node (ref "R127") (pin "2") (pinfunction "2_2") (pintype "passive"))
      (node (ref "R228") (pin "1") (pinfunction "1_1") (pintype "passive"))
      (node (ref "U64") (pin "14") (pinfunction "VCC_14") (pintype "power_in"))
    )
    (net (code "135") (name "PNET2") (class "Default")
      (node (ref "C2") (pin "1") (pinfunction "+_1") (pintype "passive"))
      (node (ref "C235") (pin "1") (pinfunction "+_1") (pintype "passive"))
      (node (ref "C237") (pin "1") (pinfunction "+_1") (pintype "passive"))
      (node (ref "C3") (pin "1") (pinfunction "+_1") (pintype "passive"))
      (node (ref "J13") (pin "21") (pinfunction "PNET2_21") (pintype "power_in"))
      (node (ref "J13") (pin "80") (pinfunction "PNET2_80") (pintype "power_in"))
      (node (ref "R183") (pin "1") (pinfunction "1_1") (pintype "passive"))
      (node (ref "U1") (pin "5") (pinfunction "VCC_5") (pintype "power_in"))
      (node (ref "U2") (pin "8") (pinfunction "VCC_8") (pintype "power_in"))
    )
    (net (code "136") (name "PNET4") (class "Default")
      (node (ref "D39") (pin "1") (pinfunction "K_1") (pintype "passive"))
      (node (ref "D55") (pin "1") (pinfunction "K_1") (pintype "passive"))
    )
    (net (code "137") (name "PNET5") (class "Default")
      (node (ref "C243") (pin "1") (pinfunction "+_1") (pintype "passive"))
      (node (ref "C265") (pin "2") (pinfunction "-_2") (pintype "passive"))
      (node (ref "C90") (pin "2") (pinfunction "-_2") (pintype "passive"))
      (node (ref "C91") (pin "1") (pinfunction "+_1") (pintype "passive"))
      (node (ref "F2") (pin "2") (pinfunction "2_2") (pintype "passive"))
      (node (ref "J13") (pin "40") (pinfunction "PNET5_40") (pintype "power_in"))
      (node (ref "Q24") (pin "2") (pinfunction "E_2") (pintype "passive"))
      (node (ref "Q25") (pin "3") (pinfunction "E_3") (pintype "passive"))
      (node (ref "Q34") (pin "3") (pinfunction "E_3") (pintype "passive"))
      (node (ref "R122") (pin "1") (pinfunction "1_1") (pintype "passive"))
      (node (ref "R123") (pin "1") (pinfunction "1_1") (pintype "passive"))
      (node (ref "R124") (pin "1") (pinfunction "1_1") (pintype "passive"))
      (node (ref "R125") (pin "2") (pinfunction "2_2") (pintype "passive"))
      (node (ref "R135") (pin "2") (pinfunction "2_2") (pintype "passive"))
      (node (ref "R188") (pin "2") (pinfunction "2_2") (pintype "passive"))
      (node (ref "R192") (pin "2") (pinfunction "2_2") (pintype "passive"))
      (node (ref "R193") (pin "2") (pinfunction "2_2") (pintype "passive"))
      (node (ref "R302") (pin "1") (pinfunction "1_1") (pintype "passive"))
      (node (ref "R303") (pin "1") (pinfunction "1_1") (pintype "passive"))
      (node (ref "R305") (pin "1") (pinfunction "1_1") (pintype "passive"))
      (node (ref "R306") (pin "1") (pinfunction "1_1") (pintype "passive"))
      (node (ref "R307") (pin "1") (pinfunction "1_1") (pintype "passive"))
      (node (ref "R309") (pin "1") (pinfunction "1_1") (pintype "passive"))
      (node (ref "R311") (pin "2") (pinfunction "2_2") (pintype "passive"))
      (node (ref "U20") (pin "8") (pinfunction "VCC_8") (pintype "power_in"))
      (node (ref "U26") (pin "8") (pinfunction "VCC_8") (pintype "power_in"))
      (node (ref "U57") (pin "14") (pinfunction "VCC_14") (pintype "power_in"))
      (node (ref "U71") (pin "14") (pinfunction "VCC_14") (pintype "power_in"))
    )
    (net (code "138") (name "PNET7") (class "Default")
      (node (ref "R130") (pin "1") (pinfunction "1_1") (pintype "passive"))
      (node (ref "R139") (pin "1") (pinfunction "1_1") (pintype "passive"))
      (node (ref "R144") (pin "1") (pinfunction "1_1") (pintype "passive"))
    )
    (net (code "139") (name "VCC") (class "Default")
      (node (ref "C88") (pin "2") (pinfunction "-_2") (pintype "passive"))
      (node (ref "J8") (pin "2") (pinfunction "VCC_2") (pintype "power_in"))
      (node (ref "J8") (pin "25") (pinfunction "VCC_25") (pintype "power_in"))
    )
    (net (code "140") (name "unconnected-(D59-A-Pad1)") (class "Default")
      (node (ref "D59") (pin "1") (pinfunction "A_1") (pintype "passive+no_connect"))
    )
    (net (code "141") (name "unconnected-(D59-A-Pad3)") (class "Default")
      (node (ref "D59") (pin "3") (pinfunction "A_3") (pintype "passive+no_connect"))
    )
    (net (code "142") (name "unconnected-(D59-K-Pad2)") (class "Default")
      (node (ref "D59") (pin "2") (pinfunction "K_2") (pintype "passive+no_connect"))
    )
    (net (code "143") (name "unconnected-(J13-NC-Pad32)") (class "Default")
      (node (ref "J13") (pin "32") (pinfunction "NC_32") (pintype "input"))
    )
    (net (code "144") (name "unconnected-(J13-NC-Pad34)") (class "Default")
      (node (ref "J13") (pin "34") (pinfunction "NC_34") (pintype "input"))
    )
    (net (code "145") (name "unconnected-(J13-NC-Pad35)") (class "Default")
      (node (ref "J13") (pin "35") (pinfunction "NC_35") (pintype "input"))
    )
    (net (code "146") (name "unconnected-(J13-NC-Pad37)") (class "Default")
      (node (ref "J13") (pin "37") (pinfunction "NC_37") (pintype "input"))
    )
    (net (code "147") (name "unconnected-(J13-NC-Pad43)") (class "Default")
      (node (ref "J13") (pin "43") (pinfunction "NC_43") (pintype "input"))
    )
    (net (code "148") (name "unconnected-(J13-NC-Pad44)") (class "Default")
      (node (ref "J13") (pin "44") (pinfunction "NC_44") (pintype "input"))
    )
    (net (code "149") (name "unconnected-(J13-NC-Pad45)") (class "Default")
      (node (ref "J13") (pin "45") (pinfunction "NC_45") (pintype "input"))
    )
    (net (code "150") (name "unconnected-(J13-NC-Pad47)") (class "Default")
      (node (ref "J13") (pin "47") (pinfunction "NC_47") (pintype "input"))
    )
    (net (code "151") (name "unconnected-(J13-NC-Pad49)") (class "Default")
      (node (ref "J13") (pin "49") (pinfunction "NC_49") (pintype "input"))
    )
    (net (code "152") (name "unconnected-(U1-NC-Pad1)") (class "Default")
      (node (ref "U1") (pin "1") (pinfunction "NC_1") (pintype "input"))
    )
    (net (code "153") (name "unconnected-(U3-IRDA_LED_K-Pad4)") (class "Default")
      (node (ref "U3") (pin "4") (pinfunction "IRDA_LED_K_4") (pintype "passive+no_connect"))
    )
    (net (code "154") (name "unconnected-(U71-Pad6)") (class "Default")
      (node (ref "U71") (pin "6") (pinfunction "6_6") (pintype "output+no_connect"))
    )
  )
)
